# MYO-BT.net
KiCad netlist of a schematic drawn in Altium Designer
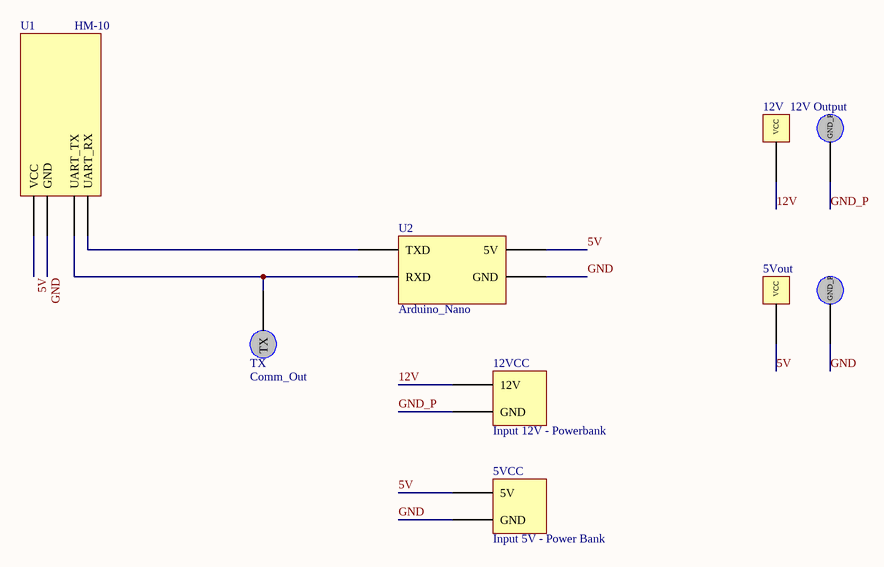
[diagram p0: MYO-BT.SchDoc]

(export (version "E")
  (design (tool "Eeschema 10.0.6"))
  (components
    (comp (ref "5VCC")
      (value "Input 5V - Power Bank")
      (footprint "5VCC")
      (libsource (lib "MYO-BT_SchLib") (part "Input 5V - Power Bank"))
    )
    (comp (ref "5Vout")
      (value "12V Output")
      (footprint "Vout")
      (libsource (lib "MYO-BT_SchLib") (part "12V Output"))
    )
    (comp (ref "12V")
      (value "12V Output")
      (footprint "Vout")
      (libsource (lib "MYO-BT_SchLib") (part "12V Output"))
    )
    (comp (ref "12VCC")
      (value "Input 12V - Powerbank")
      (footprint "12VCC")
      (libsource (lib "MYO-BT_SchLib") (part "Input 12V - Powerbank"))
    )
    (comp (ref "TX")
      (value "Comm_Out")
      (footprint "Comm_Out")
      (libsource (lib "MYO-BT_SchLib") (part "Comm_Out"))
    )
    (comp (ref "U1")
      (value "HM-10")
      (footprint "HM-10")
      (description "HM-10, just with necessary pins for this application")
      (libsource (lib "MYO-BT_SchLib") (part "HM-10_Basic"))
    )
    (comp (ref "U2")
      (value "Arduino_Nano")
      (footprint "Arduino Nano")
      (description "Arduino Nano with only the necessary pins for this application.")
      (libsource (lib "MYO-BT_SchLib") (part "Arduino_Nano_Basic"))
    )
  )
  (nets
    (net (code "1") (name "/5V") (class "Default")
      (node (ref "5VCC") (pin "1") (pinfunction "5V_1") (pintype "passive"))
      (node (ref "5Vout") (pin "1") (pinfunction "VCC_1") (pintype "passive"))
      (node (ref "U1") (pin "1") (pinfunction "VCC_1") (pintype "passive"))
      (node (ref "U2") (pin "5V") (pinfunction "5V_5V") (pintype "passive"))
    )
    (net (code "2") (name "/12V") (class "Default")
      (node (ref "12V") (pin "1") (pinfunction "VCC_1") (pintype "passive"))
      (node (ref "12VCC") (pin "1") (pinfunction "12V_1") (pintype "passive"))
    )
    (net (code "3") (name "/GND") (class "Default")
      (node (ref "5VCC") (pin "2") (pinfunction "GND_2") (pintype "passive"))
      (node (ref "5Vout") (pin "2") (pinfunction "GND_P_2") (pintype "passive"))
      (node (ref "U1") (pin "2") (pinfunction "GND_2") (pintype "passive"))
      (node (ref "U2") (pin "GND") (pinfunction "GND_GND") (pintype "passive"))
    )
    (net (code "4") (name "/GND_P") (class "Default")
      (node (ref "12V") (pin "2") (pinfunction "GND_P_2") (pintype "passive"))
      (node (ref "12VCC") (pin "2") (pinfunction "GND_2") (pintype "passive"))
    )
    (net (code "5") (name "Net-(TX-TX)") (class "Default")
      (node (ref "TX") (pin "1") (pinfunction "TX_1") (pintype "passive"))
      (node (ref "U1") (pin "3") (pinfunction "UART_TX_3") (pintype "passive"))
      (node (ref "U2") (pin "RXD") (pinfunction "RXD_RXD") (pintype "passive"))
    )
    (net (code "6") (name "Net-(U1-UART_RX)") (class "Default")
      (node (ref "U1") (pin "4") (pinfunction "UART_RX_4") (pintype "passive"))
      (node (ref "U2") (pin "TXD") (pinfunction "TXD_TXD") (pintype "passive"))
    )
  )
)
